# ASBB_GiantGecko_v2.net
KiCad netlist of a schematic drawn in Altium Designer
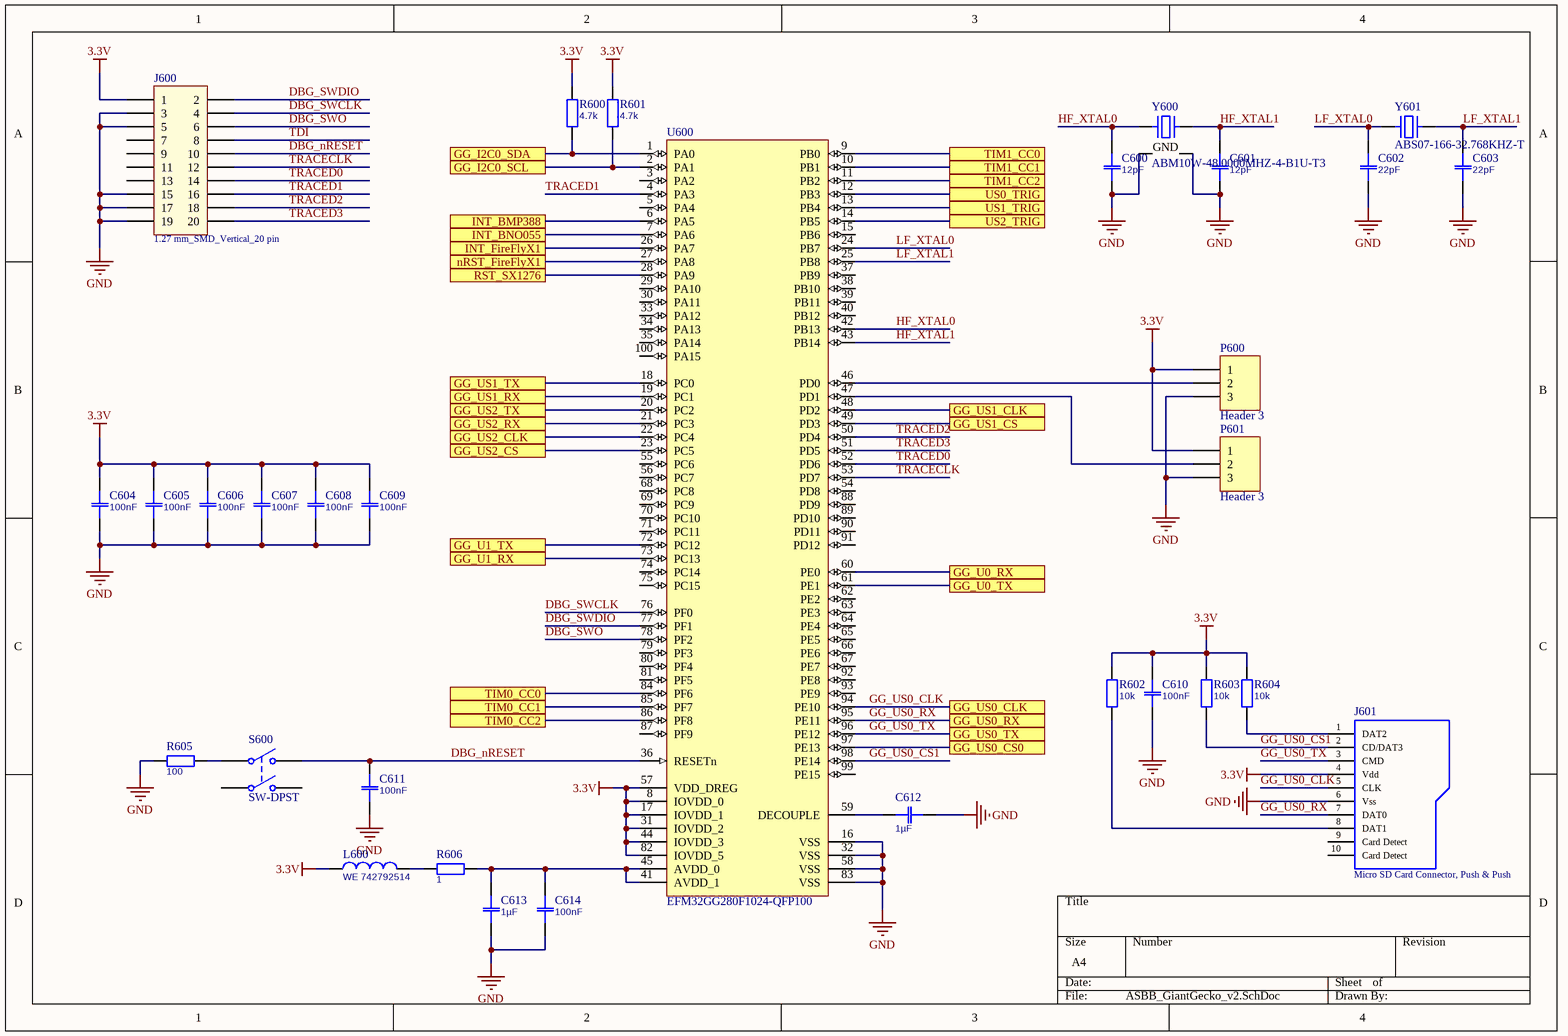
[diagram p0: ASBB_GiantGecko_v2.SchDoc]

(export (version "E")
  (design (tool "Eeschema 10.0.6"))
  (components
    (comp (ref "C600")
      (value "12pF")
      (footprint "0603")
      (description "Capacitor")
      (fields (field (name "PARTNUMBER") "?"))
      (libsource (lib "FZI") (part "Capacitor"))
    )
    (comp (ref "C601")
      (value "12pF")
      (footprint "0603")
      (description "Capacitor")
      (fields (field (name "PARTNUMBER") "?"))
      (libsource (lib "FZI") (part "Capacitor"))
    )
    (comp (ref "C602")
      (value "22pF")
      (footprint "0603")
      (description "Capacitor")
      (fields (field (name "PARTNUMBER") "?"))
      (libsource (lib "FZI") (part "Capacitor"))
    )
    (comp (ref "C603")
      (value "22pF")
      (footprint "0603")
      (description "Capacitor")
      (fields (field (name "PARTNUMBER") "?"))
      (libsource (lib "FZI") (part "Capacitor"))
    )
    (comp (ref "C604")
      (value "100nF")
      (footprint "0603")
      (description "Capacitor")
      (fields (field (name "PARTNUMBER") "?"))
      (libsource (lib "FZI") (part "Capacitor"))
    )
    (comp (ref "C605")
      (value "100nF")
      (footprint "0603")
      (description "Capacitor")
      (fields (field (name "PARTNUMBER") "?"))
      (libsource (lib "FZI") (part "Capacitor"))
    )
    (comp (ref "C606")
      (value "100nF")
      (footprint "0603")
      (description "Capacitor")
      (fields (field (name "PARTNUMBER") "?"))
      (libsource (lib "FZI") (part "Capacitor"))
    )
    (comp (ref "C607")
      (value "100nF")
      (footprint "0603")
      (description "Capacitor")
      (fields (field (name "PARTNUMBER") "?"))
      (libsource (lib "FZI") (part "Capacitor"))
    )
    (comp (ref "C608")
      (value "100nF")
      (footprint "0603")
      (description "Capacitor")
      (fields (field (name "PARTNUMBER") "?"))
      (libsource (lib "FZI") (part "Capacitor"))
    )
    (comp (ref "C609")
      (value "100nF")
      (footprint "0603")
      (description "Capacitor")
      (fields (field (name "PARTNUMBER") "?"))
      (libsource (lib "FZI") (part "Capacitor"))
    )
    (comp (ref "C610")
      (value "100nF")
      (footprint "0603")
      (description "Capacitor")
      (fields (field (name "PARTNUMBER") "?"))
      (libsource (lib "FZI") (part "Capacitor"))
    )
    (comp (ref "C611")
      (value "100nF")
      (footprint "0603")
      (description "Capacitor")
      (fields (field (name "PARTNUMBER") "?"))
      (libsource (lib "FZI") (part "Capacitor"))
    )
    (comp (ref "C612")
      (value "1µF")
      (footprint "0603")
      (description "Capacitor")
      (fields (field (name "PARTNUMBER") "?"))
      (libsource (lib "FZI") (part "Capacitor"))
    )
    (comp (ref "C613")
      (value "1µF")
      (footprint "0603")
      (description "Capacitor")
      (fields (field (name "PARTNUMBER") "?"))
      (libsource (lib "FZI") (part "Capacitor"))
    )
    (comp (ref "C614")
      (value "100nF")
      (footprint "0603")
      (description "Capacitor")
      (fields (field (name "PARTNUMBER") "?"))
      (libsource (lib "FZI") (part "Capacitor"))
    )
    (comp (ref "J600")
      (value "1.27 mm_SMD_Vertical_20 pin")
      (footprint "62102021021")
      (description "Pin Header WR-PHD, pitch 1.27 mm, SMD, Vertical, dual row, 20 pin")
      (fields (field (name "PART NUMBER") "62102021021") (field (name "PUBLISHER") "Wurth Elektronik"))
      (libsource (lib "6220xx21121 (rev18a)") (part "62102021021"))
    )
    (comp (ref "J601")
      (value "Micro SD Card Connector, Push & Push")
      (footprint "693071010811")
      (description "WR-CRD Micro SD Card Connector, Push & Push, with card detection")
      (fields (field (name "PART NUMBER") "693071010811") (field (name "PUBLISHER") "Wurth Elektronik"))
      (libsource (lib "ALTIUM-WR-CRD-rev18a") (part "693071010811"))
    )
    (comp (ref "L600")
      (value "WE 742792514")
      (footprint "1812")
      (description "Inductor")
      (fields (field (name "PARTNUMBER") "?"))
      (libsource (lib "FZI") (part "Inductor"))
    )
    (comp (ref "P600")
      (value "Header 3")
      (footprint "HDR1X3")
      (description "Header, 3-Pin")
      (fields (field (name "PUBLISHER") "Altium Limited"))
      (libsource (lib "Miscellaneous Connectors") (part "Header 3"))
    )
    (comp (ref "P601")
      (value "Header 3")
      (footprint "HDR1X3")
      (description "Header, 3-Pin")
      (fields (field (name "PUBLISHER") "Altium Limited"))
      (libsource (lib "Miscellaneous Connectors") (part "Header 3"))
    )
    (comp (ref "R600")
      (value "4.7k")
      (footprint "0603")
      (description "Resistor")
      (fields (field (name "PARTNUMBER") "?"))
      (libsource (lib "FZI") (part "Resistor"))
    )
    (comp (ref "R601")
      (value "4.7k")
      (footprint "0603")
      (description "Resistor")
      (fields (field (name "PARTNUMBER") "?"))
      (libsource (lib "FZI") (part "Resistor"))
    )
    (comp (ref "R602")
      (value "10k")
      (footprint "0603")
      (description "Resistor")
      (fields (field (name "PARTNUMBER") "?"))
      (libsource (lib "FZI") (part "Resistor"))
    )
    (comp (ref "R603")
      (value "10k")
      (footprint "0603")
      (description "Resistor")
      (fields (field (name "PARTNUMBER") "?"))
      (libsource (lib "FZI") (part "Resistor"))
    )
    (comp (ref "R604")
      (value "10k")
      (footprint "0603")
      (description "Resistor")
      (fields (field (name "PARTNUMBER") "?"))
      (libsource (lib "FZI") (part "Resistor"))
    )
    (comp (ref "R605")
      (value "100")
      (footprint "0603")
      (description "Resistor")
      (fields (field (name "PARTNUMBER") "?"))
      (libsource (lib "FZI") (part "Resistor"))
    )
    (comp (ref "R606")
      (value "1")
      (footprint "0603")
      (description "Resistor")
      (fields (field (name "PARTNUMBER") "?"))
      (libsource (lib "FZI") (part "Resistor"))
    )
    (comp (ref "S600")
      (value "SW-DPST")
      (footprint "DPST-4")
      (description "Double-Pole, Single-Throw Switch")
      (fields (field (name "PUBLISHER") "Altium Limited"))
      (libsource (lib "Miscellaneous Devices") (part "SW-DPST"))
    )
    (comp (ref "U600")
      (value "EFM32GG280F1024-QFP100")
      (footprint "ENMR-LQFP100_N")
      (fields (field (name "GENERIC PART NUMBER") "EFM32GG280"))
      (libsource (lib "Silicon Labs Energy Micro EFM32") (part "EFM32GG280F1024-QFP100"))
    )
    (comp (ref "Y600")
      (value "ABM10W-48.0000MHZ-4-B1U-T3")
      (description "SMT Crystal")
      (libsource (lib "Crystals") (part "Abracon Crystal ABM10"))
    )
    (comp (ref "Y601")
      (value "ABS07-166-32.768KHZ-T")
      (description "SMT Crystal")
      (libsource (lib "Crystals") (part "Abracon Crystal ABS06"))
    )
  )
  (nets
    (net (code "1") (name "/DBG_SWCLK") (class "Default")
      (node (ref "J600") (pin "4") (pinfunction "4_4") (pintype "passive"))
      (node (ref "U600") (pin "76") (pinfunction "PF0_76") (pintype "bidirectional"))
    )
    (net (code "2") (name "/DBG_SWDIO") (class "Default")
      (node (ref "J600") (pin "2") (pinfunction "2_2") (pintype "passive"))
      (node (ref "U600") (pin "77") (pinfunction "PF1_77") (pintype "bidirectional"))
    )
    (net (code "3") (name "/DBG_SWO") (class "Default")
      (node (ref "J600") (pin "6") (pinfunction "6_6") (pintype "passive"))
      (node (ref "U600") (pin "78") (pinfunction "PF2_78") (pintype "bidirectional"))
    )
    (net (code "4") (name "/DBG_nRESET") (class "Default")
      (node (ref "C611") (pin "1") (pinfunction "1_1") (pintype "passive"))
      (node (ref "J600") (pin "10") (pinfunction "10_10") (pintype "passive"))
      (node (ref "S600") (pin "2") (pinfunction "NO1_2") (pintype "passive"))
      (node (ref "U600") (pin "36") (pinfunction "RESETn_36") (pintype "input"))
    )
    (net (code "5") (name "/GG_I2C0_SCL") (class "Default")
      (node (ref "R601") (pin "1") (pinfunction "1_1") (pintype "passive"))
      (node (ref "U600") (pin "2") (pinfunction "PA1_2") (pintype "bidirectional"))
    )
    (net (code "6") (name "/GG_I2C0_SDA") (class "Default")
      (node (ref "R600") (pin "1") (pinfunction "1_1") (pintype "passive"))
      (node (ref "U600") (pin "1") (pinfunction "PA0_1") (pintype "bidirectional"))
    )
    (net (code "7") (name "/GG_U0_RX") (class "Default")
      (node (ref "U600") (pin "60") (pinfunction "PE0_60") (pintype "bidirectional"))
    )
    (net (code "8") (name "/GG_U0_TX") (class "Default")
      (node (ref "U600") (pin "61") (pinfunction "PE1_61") (pintype "bidirectional"))
    )
    (net (code "9") (name "/GG_U1_RX") (class "Default")
      (node (ref "U600") (pin "73") (pinfunction "PC13_73") (pintype "bidirectional"))
    )
    (net (code "10") (name "/GG_U1_TX") (class "Default")
      (node (ref "U600") (pin "72") (pinfunction "PC12_72") (pintype "bidirectional"))
    )
    (net (code "11") (name "/GG_US0_CLK") (class "Default")
      (node (ref "J601") (pin "5") (pinfunction "CLK_5") (pintype "passive"))
      (node (ref "U600") (pin "94") (pinfunction "PE10_94") (pintype "bidirectional"))
    )
    (net (code "12") (name "/GG_US0_CS0") (class "Default")
      (node (ref "U600") (pin "97") (pinfunction "PE13_97") (pintype "bidirectional"))
    )
    (net (code "13") (name "/GG_US0_CS1") (class "Default")
      (node (ref "J601") (pin "2") (pinfunction "CD/DAT3_2") (pintype "passive"))
      (node (ref "R603") (pin "1") (pinfunction "1_1") (pintype "passive"))
      (node (ref "U600") (pin "98") (pinfunction "PE14_98") (pintype "bidirectional"))
    )
    (net (code "14") (name "/GG_US0_RX") (class "Default")
      (node (ref "J601") (pin "7") (pinfunction "DAT0_7") (pintype "passive"))
      (node (ref "U600") (pin "95") (pinfunction "PE11_95") (pintype "bidirectional"))
    )
    (net (code "15") (name "/GG_US0_TX") (class "Default")
      (node (ref "J601") (pin "3") (pinfunction "CMD_3") (pintype "passive"))
      (node (ref "U600") (pin "96") (pinfunction "PE12_96") (pintype "bidirectional"))
    )
    (net (code "16") (name "/GG_US1_CLK") (class "Default")
      (node (ref "U600") (pin "48") (pinfunction "PD2_48") (pintype "bidirectional"))
    )
    (net (code "17") (name "/GG_US1_CS") (class "Default")
      (node (ref "U600") (pin "49") (pinfunction "PD3_49") (pintype "bidirectional"))
    )
    (net (code "18") (name "/GG_US1_RX") (class "Default")
      (node (ref "U600") (pin "19") (pinfunction "PC1_19") (pintype "bidirectional"))
    )
    (net (code "19") (name "/GG_US1_TX") (class "Default")
      (node (ref "U600") (pin "18") (pinfunction "PC0_18") (pintype "bidirectional"))
    )
    (net (code "20") (name "/GG_US2_CLK") (class "Default")
      (node (ref "U600") (pin "22") (pinfunction "PC4_22") (pintype "bidirectional"))
    )
    (net (code "21") (name "/GG_US2_CS") (class "Default")
      (node (ref "U600") (pin "23") (pinfunction "PC5_23") (pintype "bidirectional"))
    )
    (net (code "22") (name "/GG_US2_RX") (class "Default")
      (node (ref "U600") (pin "21") (pinfunction "PC3_21") (pintype "bidirectional"))
    )
    (net (code "23") (name "/GG_US2_TX") (class "Default")
      (node (ref "U600") (pin "20") (pinfunction "PC2_20") (pintype "bidirectional"))
    )
    (net (code "24") (name "/HF_XTAL0") (class "Default")
      (node (ref "C600") (pin "1") (pinfunction "1_1") (pintype "passive"))
      (node (ref "U600") (pin "42") (pinfunction "PB13_42") (pintype "bidirectional"))
      (node (ref "Y600") (pin "1") (pinfunction "1_1") (pintype "passive"))
    )
    (net (code "25") (name "/HF_XTAL1") (class "Default")
      (node (ref "C601") (pin "1") (pinfunction "1_1") (pintype "passive"))
      (node (ref "U600") (pin "43") (pinfunction "PB14_43") (pintype "bidirectional"))
      (node (ref "Y600") (pin "3") (pinfunction "3_3") (pintype "passive"))
    )
    (net (code "26") (name "/INT_BMP388") (class "Default")
      (node (ref "U600") (pin "6") (pinfunction "PA5_6") (pintype "bidirectional"))
    )
    (net (code "27") (name "/INT_BNO055") (class "Default")
      (node (ref "U600") (pin "7") (pinfunction "PA6_7") (pintype "bidirectional"))
    )
    (net (code "28") (name "/INT_FireFlyX1") (class "Default")
      (node (ref "U600") (pin "26") (pinfunction "PA7_26") (pintype "bidirectional"))
    )
    (net (code "29") (name "/LF_XTAL0") (class "Default")
      (node (ref "C602") (pin "1") (pinfunction "1_1") (pintype "passive"))
      (node (ref "U600") (pin "24") (pinfunction "PB7_24") (pintype "bidirectional"))
      (node (ref "Y601") (pin "1") (pinfunction "1_1") (pintype "passive"))
    )
    (net (code "30") (name "/LF_XTAL1") (class "Default")
      (node (ref "C603") (pin "1") (pinfunction "1_1") (pintype "passive"))
      (node (ref "U600") (pin "25") (pinfunction "PB8_25") (pintype "bidirectional"))
      (node (ref "Y601") (pin "2") (pinfunction "2_2") (pintype "passive"))
    )
    (net (code "31") (name "/RST_SX1276") (class "Default")
      (node (ref "U600") (pin "28") (pinfunction "PA9_28") (pintype "bidirectional"))
    )
    (net (code "32") (name "/TDI") (class "Default")
      (node (ref "J600") (pin "8") (pinfunction "8_8") (pintype "passive"))
    )
    (net (code "33") (name "/TIM0_CC0") (class "Default")
      (node (ref "U600") (pin "84") (pinfunction "PF6_84") (pintype "bidirectional"))
    )
    (net (code "34") (name "/TIM0_CC1") (class "Default")
      (node (ref "U600") (pin "85") (pinfunction "PF7_85") (pintype "bidirectional"))
    )
    (net (code "35") (name "/TIM0_CC2") (class "Default")
      (node (ref "U600") (pin "86") (pinfunction "PF8_86") (pintype "bidirectional"))
    )
    (net (code "36") (name "/TIM1_CC0") (class "Default")
      (node (ref "U600") (pin "9") (pinfunction "PB0_9") (pintype "bidirectional"))
    )
    (net (code "37") (name "/TIM1_CC1") (class "Default")
      (node (ref "U600") (pin "10") (pinfunction "PB1_10") (pintype "bidirectional"))
    )
    (net (code "38") (name "/TIM1_CC2") (class "Default")
      (node (ref "U600") (pin "11") (pinfunction "PB2_11") (pintype "bidirectional"))
    )
    (net (code "39") (name "/TRACECLK") (class "Default")
      (node (ref "J600") (pin "12") (pinfunction "12_12") (pintype "passive"))
      (node (ref "U600") (pin "53") (pinfunction "PD7_53") (pintype "bidirectional"))
    )
    (net (code "40") (name "/TRACED0") (class "Default")
      (node (ref "J600") (pin "14") (pinfunction "14_14") (pintype "passive"))
      (node (ref "U600") (pin "52") (pinfunction "PD6_52") (pintype "bidirectional"))
    )
    (net (code "41") (name "/TRACED1") (class "Default")
      (node (ref "J600") (pin "16") (pinfunction "16_16") (pintype "passive"))
      (node (ref "U600") (pin "4") (pinfunction "PA3_4") (pintype "bidirectional"))
    )
    (net (code "42") (name "/TRACED2") (class "Default")
      (node (ref "J600") (pin "18") (pinfunction "18_18") (pintype "passive"))
      (node (ref "U600") (pin "50") (pinfunction "PD4_50") (pintype "bidirectional"))
    )
    (net (code "43") (name "/TRACED3") (class "Default")
      (node (ref "J600") (pin "20") (pinfunction "20_20") (pintype "passive"))
      (node (ref "U600") (pin "51") (pinfunction "PD5_51") (pintype "bidirectional"))
    )
    (net (code "44") (name "/US0_TRIG") (class "Default")
      (node (ref "U600") (pin "12") (pinfunction "PB3_12") (pintype "bidirectional"))
    )
    (net (code "45") (name "/US1_TRIG") (class "Default")
      (node (ref "U600") (pin "13") (pinfunction "PB4_13") (pintype "bidirectional"))
    )
    (net (code "46") (name "/US2_TRIG") (class "Default")
      (node (ref "U600") (pin "14") (pinfunction "PB5_14") (pintype "bidirectional"))
    )
    (net (code "47") (name "/nRST_FireFlyX1") (class "Default")
      (node (ref "U600") (pin "27") (pinfunction "PA8_27") (pintype "bidirectional"))
    )
    (net (code "48") (name "3.3V") (class "Default")
      (node (ref "C604") (pin "1") (pinfunction "1_1") (pintype "passive"))
      (node (ref "C605") (pin "1") (pinfunction "1_1") (pintype "passive"))
      (node (ref "C606") (pin "1") (pinfunction "1_1") (pintype "passive"))
      (node (ref "C607") (pin "1") (pinfunction "1_1") (pintype "passive"))
      (node (ref "C608") (pin "1") (pinfunction "1_1") (pintype "passive"))
      (node (ref "C609") (pin "1") (pinfunction "1_1") (pintype "passive"))
      (node (ref "C610") (pin "1") (pinfunction "1_1") (pintype "passive"))
      (node (ref "J600") (pin "1") (pinfunction "1_1") (pintype "passive"))
      (node (ref "J601") (pin "4") (pinfunction "Vdd_4") (pintype "passive"))
      (node (ref "L600") (pin "1") (pinfunction "1_1") (pintype "passive"))
      (node (ref "P600") (pin "1") (pinfunction "1_1") (pintype "passive"))
      (node (ref "P601") (pin "1") (pinfunction "1_1") (pintype "passive"))
      (node (ref "R600") (pin "2") (pinfunction "2_2") (pintype "passive"))
      (node (ref "R601") (pin "2") (pinfunction "2_2") (pintype "passive"))
      (node (ref "R602") (pin "2") (pinfunction "2_2") (pintype "passive"))
      (node (ref "R603") (pin "2") (pinfunction "2_2") (pintype "passive"))
      (node (ref "R604") (pin "2") (pinfunction "2_2") (pintype "passive"))
      (node (ref "U600") (pin "17") (pinfunction "IOVDD_1_17") (pintype "power_in"))
      (node (ref "U600") (pin "31") (pinfunction "IOVDD_2_31") (pintype "power_in"))
      (node (ref "U600") (pin "44") (pinfunction "IOVDD_3_44") (pintype "power_in"))
      (node (ref "U600") (pin "57") (pinfunction "VDD_DREG_57") (pintype "power_in"))
      (node (ref "U600") (pin "8") (pinfunction "IOVDD_0_8") (pintype "power_in"))
      (node (ref "U600") (pin "82") (pinfunction "IOVDD_5_82") (pintype "power_in"))
    )
    (net (code "49") (name "GND") (class "Default")
      (node (ref "C600") (pin "2") (pinfunction "2_2") (pintype "passive"))
      (node (ref "C601") (pin "2") (pinfunction "2_2") (pintype "passive"))
      (node (ref "C602") (pin "2") (pinfunction "2_2") (pintype "passive"))
      (node (ref "C603") (pin "2") (pinfunction "2_2") (pintype "passive"))
      (node (ref "C604") (pin "2") (pinfunction "2_2") (pintype "passive"))
      (node (ref "C605") (pin "2") (pinfunction "2_2") (pintype "passive"))
      (node (ref "C606") (pin "2") (pinfunction "2_2") (pintype "passive"))
      (node (ref "C607") (pin "2") (pinfunction "2_2") (pintype "passive"))
      (node (ref "C608") (pin "2") (pinfunction "2_2") (pintype "passive"))
      (node (ref "C609") (pin "2") (pinfunction "2_2") (pintype "passive"))
      (node (ref "C610") (pin "2") (pinfunction "2_2") (pintype "passive"))
      (node (ref "C611") (pin "2") (pinfunction "2_2") (pintype "passive"))
      (node (ref "C612") (pin "2") (pinfunction "2_2") (pintype "passive"))
      (node (ref "C613") (pin "2") (pinfunction "2_2") (pintype "passive"))
      (node (ref "C614") (pin "2") (pinfunction "2_2") (pintype "passive"))
      (node (ref "J600") (pin "15") (pinfunction "15_15") (pintype "passive"))
      (node (ref "J600") (pin "17") (pinfunction "17_17") (pintype "passive"))
      (node (ref "J600") (pin "19") (pinfunction "19_19") (pintype "passive"))
      (node (ref "J600") (pin "3") (pinfunction "3_3") (pintype "passive"))
      (node (ref "J600") (pin "5") (pinfunction "5_5") (pintype "passive"))
      (node (ref "J601") (pin "6") (pinfunction "Vss_6") (pintype "passive"))
      (node (ref "P600") (pin "3") (pinfunction "3_3") (pintype "passive"))
      (node (ref "P601") (pin "3") (pinfunction "3_3") (pintype "passive"))
      (node (ref "R605") (pin "1") (pinfunction "1_1") (pintype "passive"))
      (node (ref "U600") (pin "16") (pinfunction "VSS_16") (pintype "power_in"))
      (node (ref "U600") (pin "32") (pinfunction "VSS_32") (pintype "power_in"))
      (node (ref "U600") (pin "58") (pinfunction "VSS_58") (pintype "power_in"))
      (node (ref "U600") (pin "83") (pinfunction "VSS_83") (pintype "power_in"))
      (node (ref "Y600") (pin "2") (pinfunction "GND_2") (pintype "passive"))
      (node (ref "Y600") (pin "4") (pinfunction "GND_4") (pintype "passive"))
    )
    (net (code "50") (name "Net-(J601-DAT1)") (class "Default")
      (node (ref "J601") (pin "8") (pinfunction "DAT1_8") (pintype "passive"))
      (node (ref "R602") (pin "1") (pinfunction "1_1") (pintype "passive"))
    )
    (net (code "51") (name "Net-(J601-DAT2)") (class "Default")
      (node (ref "J601") (pin "1") (pinfunction "DAT2_1") (pintype "passive"))
      (node (ref "R604") (pin "1") (pinfunction "1_1") (pintype "passive"))
    )
    (net (code "52") (name "Net-(L600-Pad2)") (class "Default")
      (node (ref "L600") (pin "2") (pinfunction "2_2") (pintype "passive"))
      (node (ref "R606") (pin "1") (pinfunction "1_1") (pintype "passive"))
    )
    (net (code "53") (name "Net-(S600-COMMON1)") (class "Default")
      (node (ref "R605") (pin "2") (pinfunction "2_2") (pintype "passive"))
      (node (ref "S600") (pin "1") (pinfunction "COMMON1_1") (pintype "passive"))
    )
    (net (code "54") (name "Net-(U600-AVDD_0)") (class "Default")
      (node (ref "C613") (pin "1") (pinfunction "1_1") (pintype "passive"))
      (node (ref "C614") (pin "1") (pinfunction "1_1") (pintype "passive"))
      (node (ref "R606") (pin "2") (pinfunction "2_2") (pintype "passive"))
      (node (ref "U600") (pin "41") (pinfunction "AVDD_1_41") (pintype "power_in"))
      (node (ref "U600") (pin "45") (pinfunction "AVDD_0_45") (pintype "power_in"))
    )
    (net (code "55") (name "Net-(U600-DECOUPLE)") (class "Default")
      (node (ref "C612") (pin "1") (pinfunction "1_1") (pintype "passive"))
      (node (ref "U600") (pin "59") (pinfunction "DECOUPLE_59") (pintype "passive"))
    )
    (net (code "56") (name "Net-(U600-PD0)") (class "Default")
      (node (ref "P600") (pin "2") (pinfunction "2_2") (pintype "passive"))
      (node (ref "U600") (pin "46") (pinfunction "PD0_46") (pintype "bidirectional"))
    )
    (net (code "57") (name "Net-(U600-PD1)") (class "Default")
      (node (ref "P601") (pin "2") (pinfunction "2_2") (pintype "passive"))
      (node (ref "U600") (pin "47") (pinfunction "PD1_47") (pintype "bidirectional"))
    )
    (net (code "58") (name "unconnected-(J600-Pad7)") (class "Default")
      (node (ref "J600") (pin "7") (pinfunction "7_7") (pintype "passive"))
    )
    (net (code "59") (name "unconnected-(J600-Pad9)") (class "Default")
      (node (ref "J600") (pin "9") (pinfunction "9_9") (pintype "passive"))
    )
    (net (code "60") (name "unconnected-(J600-Pad11)") (class "Default")
      (node (ref "J600") (pin "11") (pinfunction "11_11") (pintype "passive"))
    )
    (net (code "61") (name "unconnected-(J600-Pad13)") (class "Default")
      (node (ref "J600") (pin "13") (pinfunction "13_13") (pintype "passive"))
    )
    (net (code "62") (name "unconnected-(J601-Card_Detect-Pad9)") (class "Default")
      (node (ref "J601") (pin "9") (pinfunction "Card_Detect_9") (pintype "passive"))
    )
    (net (code "63") (name "unconnected-(J601-Card_Detect-Pad10)") (class "Default")
      (node (ref "J601") (pin "10") (pinfunction "Card_Detect_10") (pintype "passive"))
    )
    (net (code "64") (name "unconnected-(S600-COMMON2-Pad3)") (class "Default")
      (node (ref "S600") (pin "3") (pinfunction "COMMON2_3") (pintype "passive"))
    )
    (net (code "65") (name "unconnected-(S600-NO2-Pad4)") (class "Default")
      (node (ref "S600") (pin "4") (pinfunction "NO2_4") (pintype "passive"))
    )
    (net (code "66") (name "unconnected-(U600-PA2-Pad3)") (class "Default")
      (node (ref "U600") (pin "3") (pinfunction "PA2_3") (pintype "bidirectional"))
    )
    (net (code "67") (name "unconnected-(U600-PA4-Pad5)") (class "Default")
      (node (ref "U600") (pin "5") (pinfunction "PA4_5") (pintype "bidirectional"))
    )
    (net (code "68") (name "unconnected-(U600-PA10-Pad29)") (class "Default")
      (node (ref "U600") (pin "29") (pinfunction "PA10_29") (pintype "bidirectional"))
    )
    (net (code "69") (name "unconnected-(U600-PA11-Pad30)") (class "Default")
      (node (ref "U600") (pin "30") (pinfunction "PA11_30") (pintype "bidirectional"))
    )
    (net (code "70") (name "unconnected-(U600-PA12-Pad33)") (class "Default")
      (node (ref "U600") (pin "33") (pinfunction "PA12_33") (pintype "bidirectional"))
    )
    (net (code "71") (name "unconnected-(U600-PA13-Pad34)") (class "Default")
      (node (ref "U600") (pin "34") (pinfunction "PA13_34") (pintype "bidirectional"))
    )
    (net (code "72") (name "unconnected-(U600-PA14-Pad35)") (class "Default")
      (node (ref "U600") (pin "35") (pinfunction "PA14_35") (pintype "bidirectional"))
    )
    (net (code "73") (name "unconnected-(U600-PA15-Pad100)") (class "Default")
      (node (ref "U600") (pin "100") (pinfunction "PA15_100") (pintype "bidirectional"))
    )
    (net (code "74") (name "unconnected-(U600-PB6-Pad15)") (class "Default")
      (node (ref "U600") (pin "15") (pinfunction "PB6_15") (pintype "bidirectional"))
    )
    (net (code "75") (name "unconnected-(U600-PB9-Pad37)") (class "Default")
      (node (ref "U600") (pin "37") (pinfunction "PB9_37") (pintype "bidirectional"))
    )
    (net (code "76") (name "unconnected-(U600-PB10-Pad38)") (class "Default")
      (node (ref "U600") (pin "38") (pinfunction "PB10_38") (pintype "bidirectional"))
    )
    (net (code "77") (name "unconnected-(U600-PB11-Pad39)") (class "Default")
      (node (ref "U600") (pin "39") (pinfunction "PB11_39") (pintype "bidirectional"))
    )
    (net (code "78") (name "unconnected-(U600-PB12-Pad40)") (class "Default")
      (node (ref "U600") (pin "40") (pinfunction "PB12_40") (pintype "bidirectional"))
    )
    (net (code "79") (name "unconnected-(U600-PC6-Pad55)") (class "Default")
      (node (ref "U600") (pin "55") (pinfunction "PC6_55") (pintype "bidirectional"))
    )
    (net (code "80") (name "unconnected-(U600-PC7-Pad56)") (class "Default")
      (node (ref "U600") (pin "56") (pinfunction "PC7_56") (pintype "bidirectional"))
    )
    (net (code "81") (name "unconnected-(U600-PC8-Pad68)") (class "Default")
      (node (ref "U600") (pin "68") (pinfunction "PC8_68") (pintype "bidirectional"))
    )
    (net (code "82") (name "unconnected-(U600-PC9-Pad69)") (class "Default")
      (node (ref "U600") (pin "69") (pinfunction "PC9_69") (pintype "bidirectional"))
    )
    (net (code "83") (name "unconnected-(U600-PC10-Pad70)") (class "Default")
      (node (ref "U600") (pin "70") (pinfunction "PC10_70") (pintype "bidirectional"))
    )
    (net (code "84") (name "unconnected-(U600-PC11-Pad71)") (class "Default")
      (node (ref "U600") (pin "71") (pinfunction "PC11_71") (pintype "bidirectional"))
    )
    (net (code "85") (name "unconnected-(U600-PC14-Pad74)") (class "Default")
      (node (ref "U600") (pin "74") (pinfunction "PC14_74") (pintype "bidirectional"))
    )
    (net (code "86") (name "unconnected-(U600-PC15-Pad75)") (class "Default")
      (node (ref "U600") (pin "75") (pinfunction "PC15_75") (pintype "bidirectional"))
    )
    (net (code "87") (name "unconnected-(U600-PD8-Pad54)") (class "Default")
      (node (ref "U600") (pin "54") (pinfunction "PD8_54") (pintype "bidirectional"))
    )
    (net (code "88") (name "unconnected-(U600-PD9-Pad88)") (class "Default")
      (node (ref "U600") (pin "88") (pinfunction "PD9_88") (pintype "bidirectional"))
    )
    (net (code "89") (name "unconnected-(U600-PD10-Pad89)") (class "Default")
      (node (ref "U600") (pin "89") (pinfunction "PD10_89") (pintype "bidirectional"))
    )
    (net (code "90") (name "unconnected-(U600-PD11-Pad90)") (class "Default")
      (node (ref "U600") (pin "90") (pinfunction "PD11_90") (pintype "bidirectional"))
    )
    (net (code "91") (name "unconnected-(U600-PD12-Pad91)") (class "Default")
      (node (ref "U600") (pin "91") (pinfunction "PD12_91") (pintype "bidirectional"))
    )
    (net (code "92") (name "unconnected-(U600-PE2-Pad62)") (class "Default")
      (node (ref "U600") (pin "62") (pinfunction "PE2_62") (pintype "bidirectional"))
    )
    (net (code "93") (name "unconnected-(U600-PE3-Pad63)") (class "Default")
      (node (ref "U600") (pin "63") (pinfunction "PE3_63") (pintype "bidirectional"))
    )
    (net (code "94") (name "unconnected-(U600-PE4-Pad64)") (class "Default")
      (node (ref "U600") (pin "64") (pinfunction "PE4_64") (pintype "bidirectional"))
    )
    (net (code "95") (name "unconnected-(U600-PE5-Pad65)") (class "Default")
      (node (ref "U600") (pin "65") (pinfunction "PE5_65") (pintype "bidirectional"))
    )
    (net (code "96") (name "unconnected-(U600-PE6-Pad66)") (class "Default")
      (node (ref "U600") (pin "66") (pinfunction "PE6_66") (pintype "bidirectional"))
    )
    (net (code "97") (name "unconnected-(U600-PE7-Pad67)") (class "Default")
      (node (ref "U600") (pin "67") (pinfunction "PE7_67") (pintype "bidirectional"))
    )
    (net (code "98") (name "unconnected-(U600-PE8-Pad92)") (class "Default")
      (node (ref "U600") (pin "92") (pinfunction "PE8_92") (pintype "bidirectional"))
    )
    (net (code "99") (name "unconnected-(U600-PE9-Pad93)") (class "Default")
      (node (ref "U600") (pin "93") (pinfunction "PE9_93") (pintype "bidirectional"))
    )
    (net (code "100") (name "unconnected-(U600-PE15-Pad99)") (class "Default")
      (node (ref "U600") (pin "99") (pinfunction "PE15_99") (pintype "bidirectional"))
    )
    (net (code "101") (name "unconnected-(U600-PF3-Pad79)") (class "Default")
      (node (ref "U600") (pin "79") (pinfunction "PF3_79") (pintype "bidirectional"))
    )
    (net (code "102") (name "unconnected-(U600-PF4-Pad80)") (class "Default")
      (node (ref "U600") (pin "80") (pinfunction "PF4_80") (pintype "bidirectional"))
    )
    (net (code "103") (name "unconnected-(U600-PF5-Pad81)") (class "Default")
      (node (ref "U600") (pin "81") (pinfunction "PF5_81") (pintype "bidirectional"))
    )
    (net (code "104") (name "unconnected-(U600-PF9-Pad87)") (class "Default")
      (node (ref "U600") (pin "87") (pinfunction "PF9_87") (pintype "bidirectional"))
    )
  )
)
